# IAM_20380_BREAKOUT_BOARD.net
KiCad netlist of a schematic drawn in Altium Designer
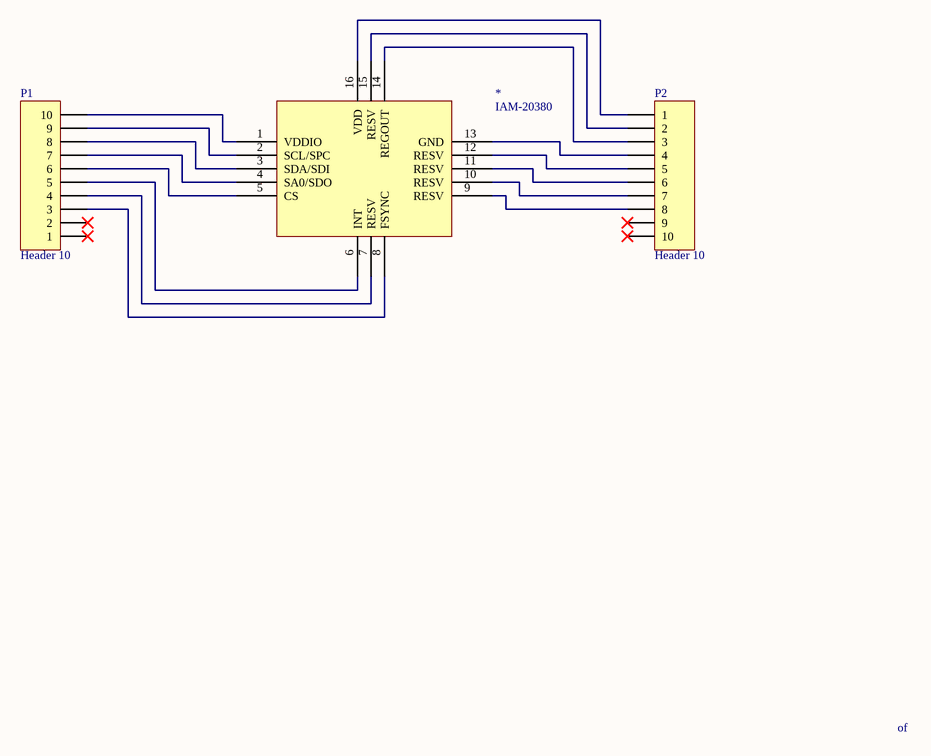
[diagram p0: IAM_20380_BREAKOUT_BOARD.SchDoc]

(export (version "E")
  (design (tool "Eeschema 10.0.6"))
  (components
    (comp (ref "*")
      (value "IAM-20380")
      (footprint "Gyro - IAM20380")
      (description "IAM-20380 High Performance Gyroscope")
      (libsource (lib "GAINS_SCH") (part "IAM-20380"))
    )
    (comp (ref "P1")
      (value "Header 10")
      (footprint "HDR1X10")
      (description "Header, 10-Pin")
      (fields (field (name "PUBLISHER") "Altium Limited"))
      (libsource (lib "") (part "Header 10_1"))
    )
    (comp (ref "P2")
      (value "Header 10")
      (footprint "HDR1X10")
      (description "Header, 10-Pin")
      (fields (field (name "PUBLISHER") "Altium Limited"))
      (libsource (lib "Miscellaneous Connectors") (part "Header 10"))
    )
  )
  (nets
    (net (code "1") (name "Net-(*-CS)") (class "Default")
      (node (ref "*") (pin "5") (pinfunction "CS_5") (pintype "passive"))
      (node (ref "P1") (pin "6") (pinfunction "6_6") (pintype "passive"))
    )
    (net (code "2") (name "Net-(*-FSYNC)") (class "Default")
      (node (ref "*") (pin "8") (pinfunction "FSYNC_8") (pintype "passive"))
      (node (ref "P1") (pin "3") (pinfunction "3_3") (pintype "passive"))
    )
    (net (code "3") (name "Net-(*-GND)") (class "Default")
      (node (ref "*") (pin "13") (pinfunction "GND_13") (pintype "passive"))
      (node (ref "P2") (pin "4") (pinfunction "4_4") (pintype "passive"))
    )
    (net (code "4") (name "Net-(*-INT)") (class "Default")
      (node (ref "*") (pin "6") (pinfunction "INT_6") (pintype "passive"))
      (node (ref "P1") (pin "5") (pinfunction "5_5") (pintype "passive"))
    )
    (net (code "5") (name "Net-(*-REGOUT)") (class "Default")
      (node (ref "*") (pin "14") (pinfunction "REGOUT_14") (pintype "passive"))
      (node (ref "P2") (pin "3") (pinfunction "3_3") (pintype "passive"))
    )
    (net (code "6") (name "Net-(*-RESV-Pad7)") (class "Default")
      (node (ref "*") (pin "7") (pinfunction "RESV_7") (pintype "passive"))
      (node (ref "P1") (pin "4") (pinfunction "4_4") (pintype "passive"))
    )
    (net (code "7") (name "Net-(*-RESV-Pad9)") (class "Default")
      (node (ref "*") (pin "9") (pinfunction "RESV_9") (pintype "passive"))
      (node (ref "P2") (pin "8") (pinfunction "8_8") (pintype "passive"))
    )
    (net (code "8") (name "Net-(*-RESV-Pad10)") (class "Default")
      (node (ref "*") (pin "10") (pinfunction "RESV_10") (pintype "passive"))
      (node (ref "P2") (pin "7") (pinfunction "7_7") (pintype "passive"))
    )
    (net (code "9") (name "Net-(*-RESV-Pad11)") (class "Default")
      (node (ref "*") (pin "11") (pinfunction "RESV_11") (pintype "passive"))
      (node (ref "P2") (pin "6") (pinfunction "6_6") (pintype "passive"))
    )
    (net (code "10") (name "Net-(*-RESV-Pad12)") (class "Default")
      (node (ref "*") (pin "12") (pinfunction "RESV_12") (pintype "passive"))
      (node (ref "P2") (pin "5") (pinfunction "5_5") (pintype "passive"))
    )
    (net (code "11") (name "Net-(*-RESV-Pad15)") (class "Default")
      (node (ref "*") (pin "15") (pinfunction "RESV_15") (pintype "passive"))
      (node (ref "P2") (pin "2") (pinfunction "2_2") (pintype "passive"))
    )
    (net (code "12") (name "Net-(*-SA0{slash}SDO)") (class "Default")
      (node (ref "*") (pin "4") (pinfunction "SA0/SDO_4") (pintype "passive"))
      (node (ref "P1") (pin "7") (pinfunction "7_7") (pintype "passive"))
    )
    (net (code "13") (name "Net-(*-SCL{slash}SPC)") (class "Default")
      (node (ref "*") (pin "2") (pinfunction "SCL/SPC_2") (pintype "passive"))
      (node (ref "P1") (pin "9") (pinfunction "9_9") (pintype "passive"))
    )
    (net (code "14") (name "Net-(*-SDA{slash}SDI)") (class "Default")
      (node (ref "*") (pin "3") (pinfunction "SDA/SDI_3") (pintype "passive"))
      (node (ref "P1") (pin "8") (pinfunction "8_8") (pintype "passive"))
    )
    (net (code "15") (name "Net-(*-VDD)") (class "Default")
      (node (ref "*") (pin "16") (pinfunction "VDD_16") (pintype "passive"))
      (node (ref "P2") (pin "1") (pinfunction "1_1") (pintype "passive"))
    )
    (net (code "16") (name "Net-(*-VDDIO)") (class "Default")
      (node (ref "*") (pin "1") (pinfunction "VDDIO_1") (pintype "passive"))
      (node (ref "P1") (pin "10") (pinfunction "10_10") (pintype "passive"))
    )
    (net (code "17") (name "unconnected-(P1-Pad1)") (class "Default")
      (node (ref "P1") (pin "1") (pinfunction "1_1") (pintype "passive+no_connect"))
    )
    (net (code "18") (name "unconnected-(P1-Pad2)") (class "Default")
      (node (ref "P1") (pin "2") (pinfunction "2_2") (pintype "passive+no_connect"))
    )
    (net (code "19") (name "unconnected-(P2-Pad9)") (class "Default")
      (node (ref "P2") (pin "9") (pinfunction "9_9") (pintype "passive+no_connect"))
    )
    (net (code "20") (name "unconnected-(P2-Pad10)") (class "Default")
      (node (ref "P2") (pin "10") (pinfunction "10_10") (pintype "passive+no_connect"))
    )
  )
)
